# PPG.net
KiCad netlist of a schematic drawn in Altium Designer
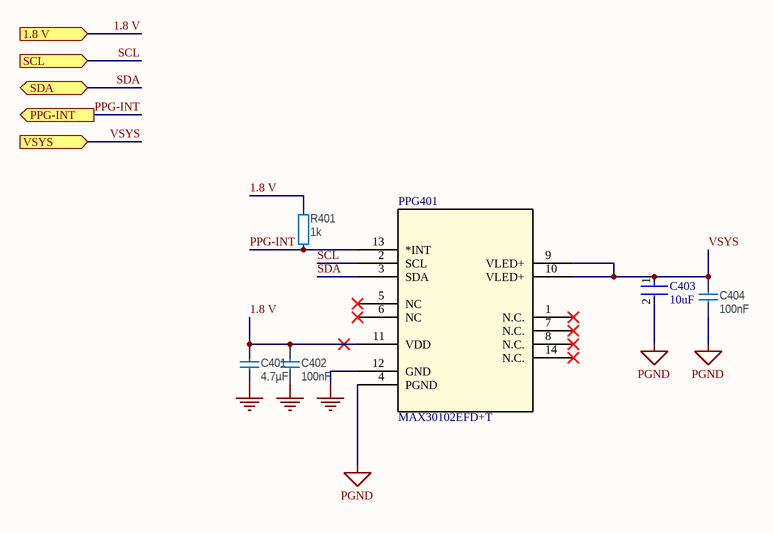
[diagram p0: PPG (MAX30102).SchDoc]

(export (version "E")
  (design (tool "Eeschema 10.0.6"))
  (components
    (comp (ref "C401")
      (value "4.7µF")
      (footprint "CAPC1608X06L")
      (description "Capacitor, X7S, ±10%")
      (fields (field (name "AUTHOR") "rsk"))
      (libsource (lib "Watch_Components") (part "C0603-4µ7-10V-X7S"))
    )
    (comp (ref "C402")
      (value "100nF")
      (footprint "CAPC0603X03L_C")
      (description "Capacitor, X7S, ±10%")
      (fields (field (name "AUTHOR") "rsk"))
      (libsource (lib "Watch_Components") (part "C0201-100n-16V-X7S"))
    )
    (comp (ref "C403")
      (value "10uF")
      (footprint "FP-GRM188-0_2-MFG")
      (description "Chip Multilayer Ceramic Capacitors for General Purpose, 0603, 10uF, X5R, 15%, 20%, 25V")
      (fields (field (name "TOLERANCE") "20%") (field (name "VOLTAGE") "25V"))
      (libsource (lib "Altium Content Vault") (part "11868f565c42a9108669ba33697ecf6"))
    )
    (comp (ref "C404")
      (value "100nF")
      (footprint "CAPC0603X03L_C")
      (description "Capacitor, X7S, ±10%")
      (fields (field (name "AUTHOR") "rsk"))
      (libsource (lib "Watch_Components") (part "C0201-100n-16V-X7S"))
    )
    (comp (ref "PPG401")
      (value "MAX30102EFD+T")
      (footprint "21-1048_F143A5+1_MXM")
      (description "High-Sensitivity Pulse Oximeter and Heart-Rate Sensor for Wearable Health")
      (fields (field (name "MANUFACTURER") "Analog Devices"))
      (libsource (lib "Watch_Components") (part "MAX30102EFD+T"))
    )
    (comp (ref "R401")
      (value "1k")
      (footprint "RESC0603X03L_C")
      (description "Resistor, ±1%, 0.05W")
      (fields (field (name "AUTHOR") "rsk"))
      (libsource (lib "Watch_Components") (part "R0201"))
    )
  )
  (nets
    (net (code "1") (name "/1.8 V") (class "Default")
      (node (ref "C401") (pin "2") (pinfunction "2_2") (pintype "passive"))
      (node (ref "C402") (pin "2") (pinfunction "2_2") (pintype "passive"))
      (node (ref "PPG401") (pin "11") (pinfunction "VDD_11") (pintype "power_in"))
      (node (ref "R401") (pin "2") (pinfunction "2_2") (pintype "passive"))
    )
    (net (code "2") (name "/PPG-INT") (class "Default")
      (node (ref "PPG401") (pin "13") (pinfunction "*INT_13") (pintype "passive"))
      (node (ref "R401") (pin "1") (pinfunction "1_1") (pintype "passive"))
    )
    (net (code "3") (name "/SCL") (class "Default")
      (node (ref "PPG401") (pin "2") (pinfunction "SCL_2") (pintype "passive"))
    )
    (net (code "4") (name "/SDA") (class "Default")
      (node (ref "PPG401") (pin "3") (pinfunction "SDA_3") (pintype "passive"))
    )
    (net (code "5") (name "/VSYS") (class "Default")
      (node (ref "C403") (pin "1") (pinfunction "1_1") (pintype "passive"))
      (node (ref "C404") (pin "2") (pinfunction "2_2") (pintype "passive"))
      (node (ref "PPG401") (pin "10") (pinfunction "VLED+_10") (pintype "passive"))
      (node (ref "PPG401") (pin "9") (pinfunction "VLED+_9") (pintype "passive"))
    )
    (net (code "6") (name "GND") (class "Default")
      (node (ref "C401") (pin "1") (pinfunction "1_1") (pintype "passive"))
      (node (ref "C402") (pin "1") (pinfunction "1_1") (pintype "passive"))
      (node (ref "PPG401") (pin "12") (pinfunction "GND_12") (pintype "power_in"))
    )
    (net (code "7") (name "PGND") (class "Default")
      (node (ref "C403") (pin "2") (pinfunction "2_2") (pintype "passive"))
      (node (ref "C404") (pin "1") (pinfunction "1_1") (pintype "passive"))
      (node (ref "PPG401") (pin "4") (pinfunction "PGND_4") (pintype "power_in"))
    )
    (net (code "8") (name "unconnected-(PPG401-N.C.-Pad1)") (class "Default")
      (node (ref "PPG401") (pin "1") (pinfunction "N.C._1") (pintype "passive+no_connect"))
    )
    (net (code "9") (name "unconnected-(PPG401-N.C.-Pad7)") (class "Default")
      (node (ref "PPG401") (pin "7") (pinfunction "N.C._7") (pintype "passive+no_connect"))
    )
    (net (code "10") (name "unconnected-(PPG401-N.C.-Pad8)") (class "Default")
      (node (ref "PPG401") (pin "8") (pinfunction "N.C._8") (pintype "passive+no_connect"))
    )
    (net (code "11") (name "unconnected-(PPG401-N.C.-Pad14)") (class "Default")
      (node (ref "PPG401") (pin "14") (pinfunction "N.C._14") (pintype "passive+no_connect"))
    )
    (net (code "12") (name "unconnected-(PPG401-NC-Pad5)") (class "Default")
      (node (ref "PPG401") (pin "5") (pinfunction "NC_5") (pintype "passive+no_connect"))
    )
    (net (code "13") (name "unconnected-(PPG401-NC-Pad6)") (class "Default")
      (node (ref "PPG401") (pin "6") (pinfunction "NC_6") (pintype "passive+no_connect"))
    )
  )
)
